# eu-ir.net
KiCad netlist of a schematic drawn in EAGLE
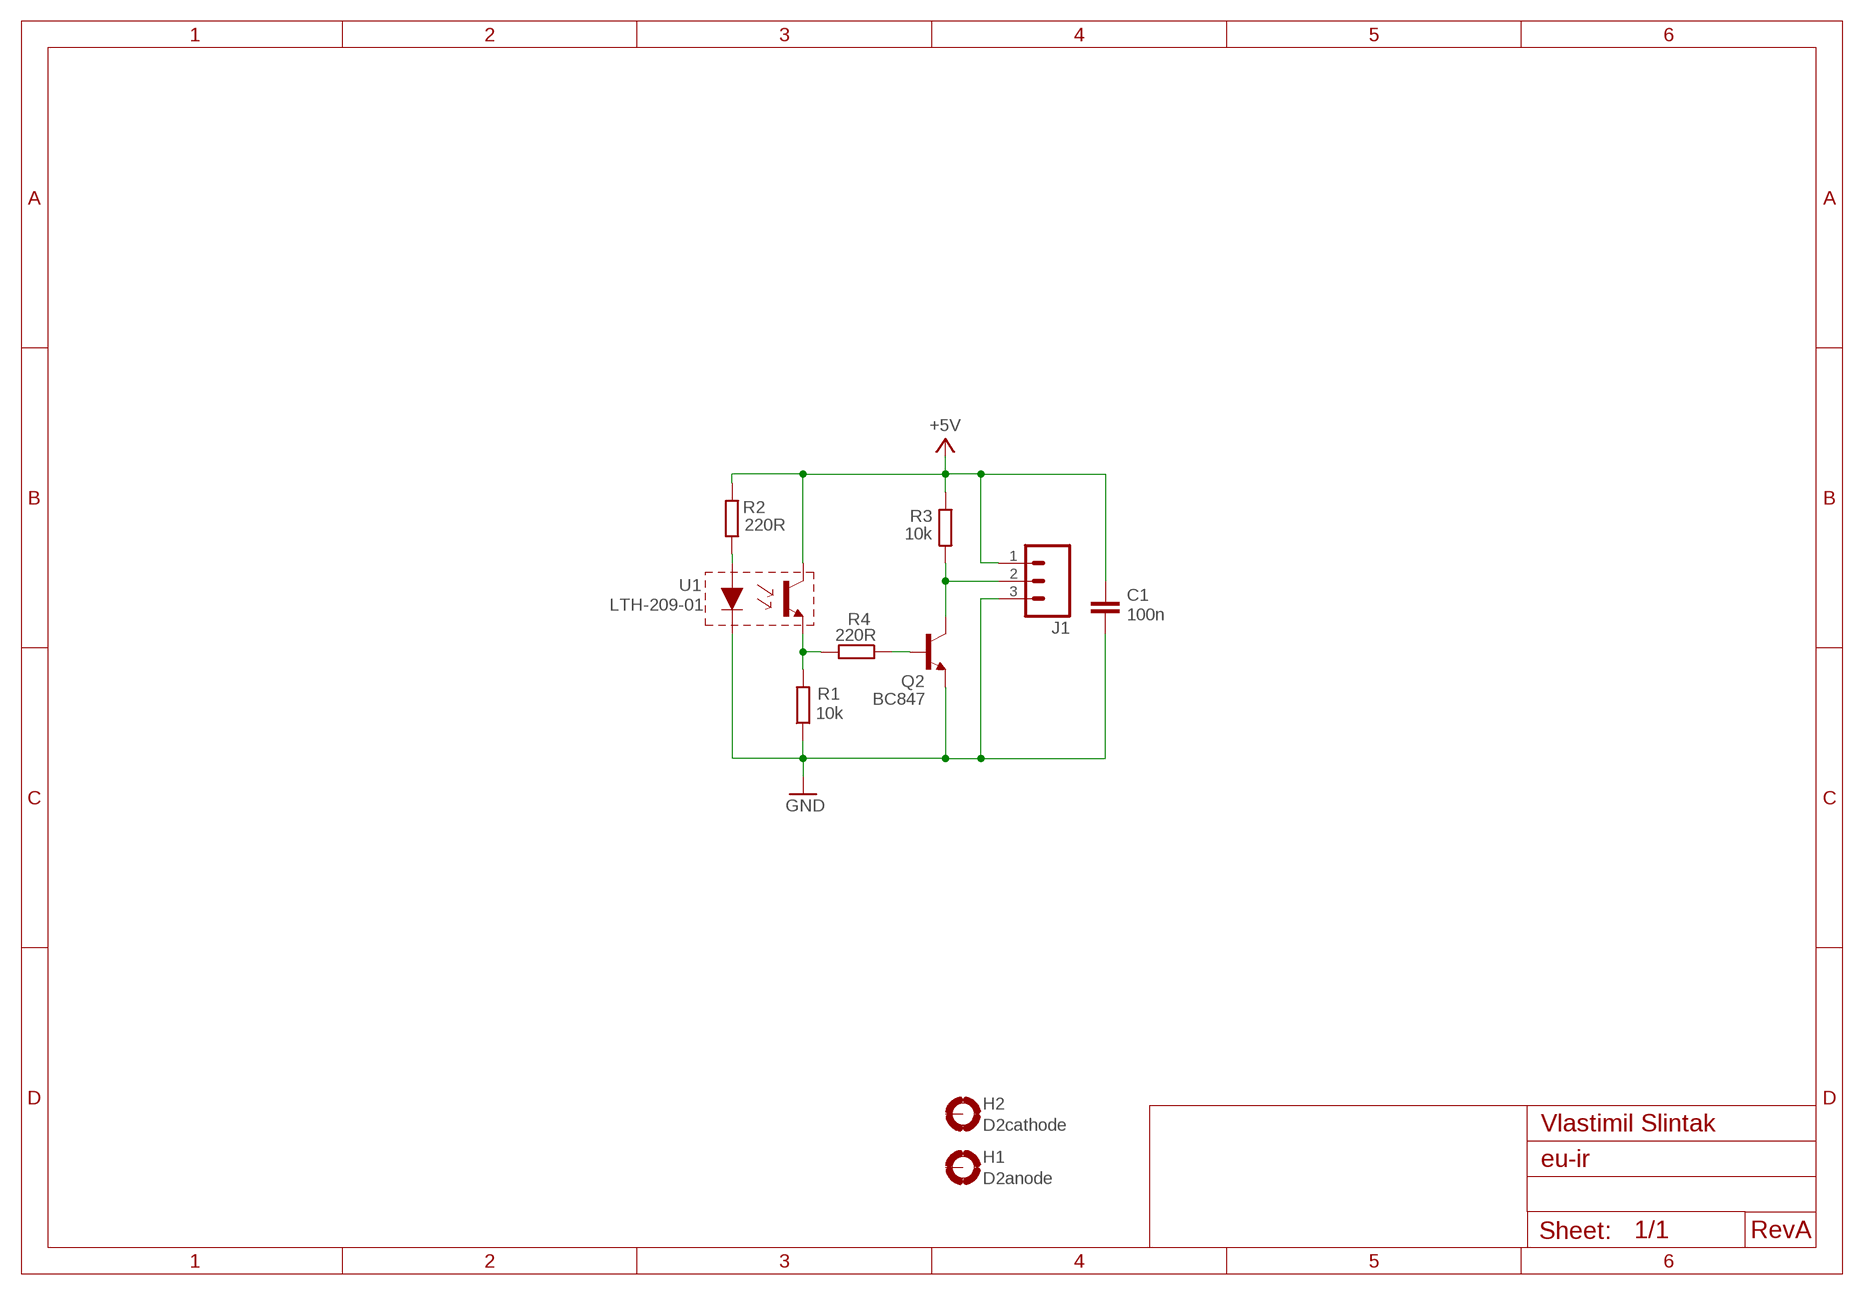
[diagram p0: schematic, sheet 1]

(export (version "E")
  (design (tool "Eeschema 10.0.6"))
  (components
    (comp (ref "C1")
      (value "100n")
      (footprint "eagle-import:C0603")
      (libsource (lib "eagle-import") (part "C-EUC0603"))
    )
    (comp (ref "H1")
      (value "D2anode")
      (footprint "eagle-import:4,1-PAD")
      (libsource (lib "eagle-import") (part "MOUNT-PAD-ROUND4.1"))
    )
    (comp (ref "H2")
      (value "D2cathode")
      (footprint "eagle-import:4,1-PAD")
      (libsource (lib "eagle-import") (part "MOUNT-PAD-ROUND4.1"))
    )
    (comp (ref "J1")
      (value "M03POLAR")
      (footprint "eagle-import:MOLEX-1X3")
      (libsource (lib "eagle-import") (part "M03POLAR"))
    )
    (comp (ref "Q2")
      (value "BC847")
      (footprint "eagle-import:SOT23")
      (libsource (lib "eagle-import") (part "BC847SMDALT1"))
    )
    (comp (ref "R1")
      (value "10k")
      (footprint "eagle-import:R0603")
      (libsource (lib "eagle-import") (part "R-EU_R0603"))
    )
    (comp (ref "R2")
      (value "220R")
      (footprint "eagle-import:R0603")
      (libsource (lib "eagle-import") (part "R-EU_R0603"))
    )
    (comp (ref "R3")
      (value "10k")
      (footprint "eagle-import:R0603")
      (libsource (lib "eagle-import") (part "R-EU_R0603"))
    )
    (comp (ref "R4")
      (value "220R")
      (footprint "eagle-import:R0603")
      (libsource (lib "eagle-import") (part "R-EU_R0603"))
    )
    (comp (ref "U1")
      (value "LTH-209-01")
      (footprint "eagle-import:LTH209")
      (libsource (lib "eagle-import") (part "LTH-209-01"))
    )
  )
  (nets
    (net (code "1") (name "+5V") (class "Default")
      (node (ref "C1") (pin "1") (pinfunction "1_1") (pintype "passive"))
      (node (ref "J1") (pin "1") (pinfunction "1_1") (pintype "passive"))
      (node (ref "R2") (pin "2") (pinfunction "2_2") (pintype "passive"))
      (node (ref "R3") (pin "1") (pinfunction "1_1") (pintype "passive"))
      (node (ref "U1") (pin "T4") (pinfunction "C_T4") (pintype "passive"))
    )
    (net (code "2") (name "GND") (class "Default")
      (node (ref "C1") (pin "2") (pinfunction "2_2") (pintype "passive"))
      (node (ref "J1") (pin "3") (pinfunction "3_3") (pintype "passive"))
      (node (ref "Q2") (pin "2") (pinfunction "E_2") (pintype "passive"))
      (node (ref "R1") (pin "1") (pinfunction "1_1") (pintype "passive"))
      (node (ref "U1") (pin "D2") (pinfunction "D-_D2") (pintype "passive"))
    )
    (net (code "3") (name "Net-(Q2-B)") (class "Default")
      (node (ref "Q2") (pin "1") (pinfunction "B_1") (pintype "passive"))
      (node (ref "R4") (pin "1") (pinfunction "1_1") (pintype "passive"))
    )
    (net (code "4") (name "Net-(Q2-C)") (class "Default")
      (node (ref "J1") (pin "2") (pinfunction "2_2") (pintype "passive"))
      (node (ref "Q2") (pin "3") (pinfunction "C_3") (pintype "passive"))
      (node (ref "R3") (pin "2") (pinfunction "2_2") (pintype "passive"))
    )
    (net (code "5") (name "Net-(U1-D+)") (class "Default")
      (node (ref "R2") (pin "1") (pinfunction "1_1") (pintype "passive"))
      (node (ref "U1") (pin "D1") (pinfunction "D+_D1") (pintype "passive"))
    )
    (net (code "6") (name "Net-(U1-E)") (class "Default")
      (node (ref "R1") (pin "2") (pinfunction "2_2") (pintype "passive"))
      (node (ref "R4") (pin "2") (pinfunction "2_2") (pintype "passive"))
      (node (ref "U1") (pin "T3") (pinfunction "E_T3") (pintype "passive"))
    )
    (net (code "7") (name "unconnected-(H1-MOUNT-PadB4,1)") (class "Default")
      (node (ref "H1") (pin "B4,1") (pinfunction "MOUNT_B4,1") (pintype "passive"))
    )
    (net (code "8") (name "unconnected-(H2-MOUNT-PadB4,1)") (class "Default")
      (node (ref "H2") (pin "B4,1") (pinfunction "MOUNT_B4,1") (pintype "passive"))
    )
  )
)
